# Sheet1.net
KiCad netlist of a schematic drawn in Altium Designer
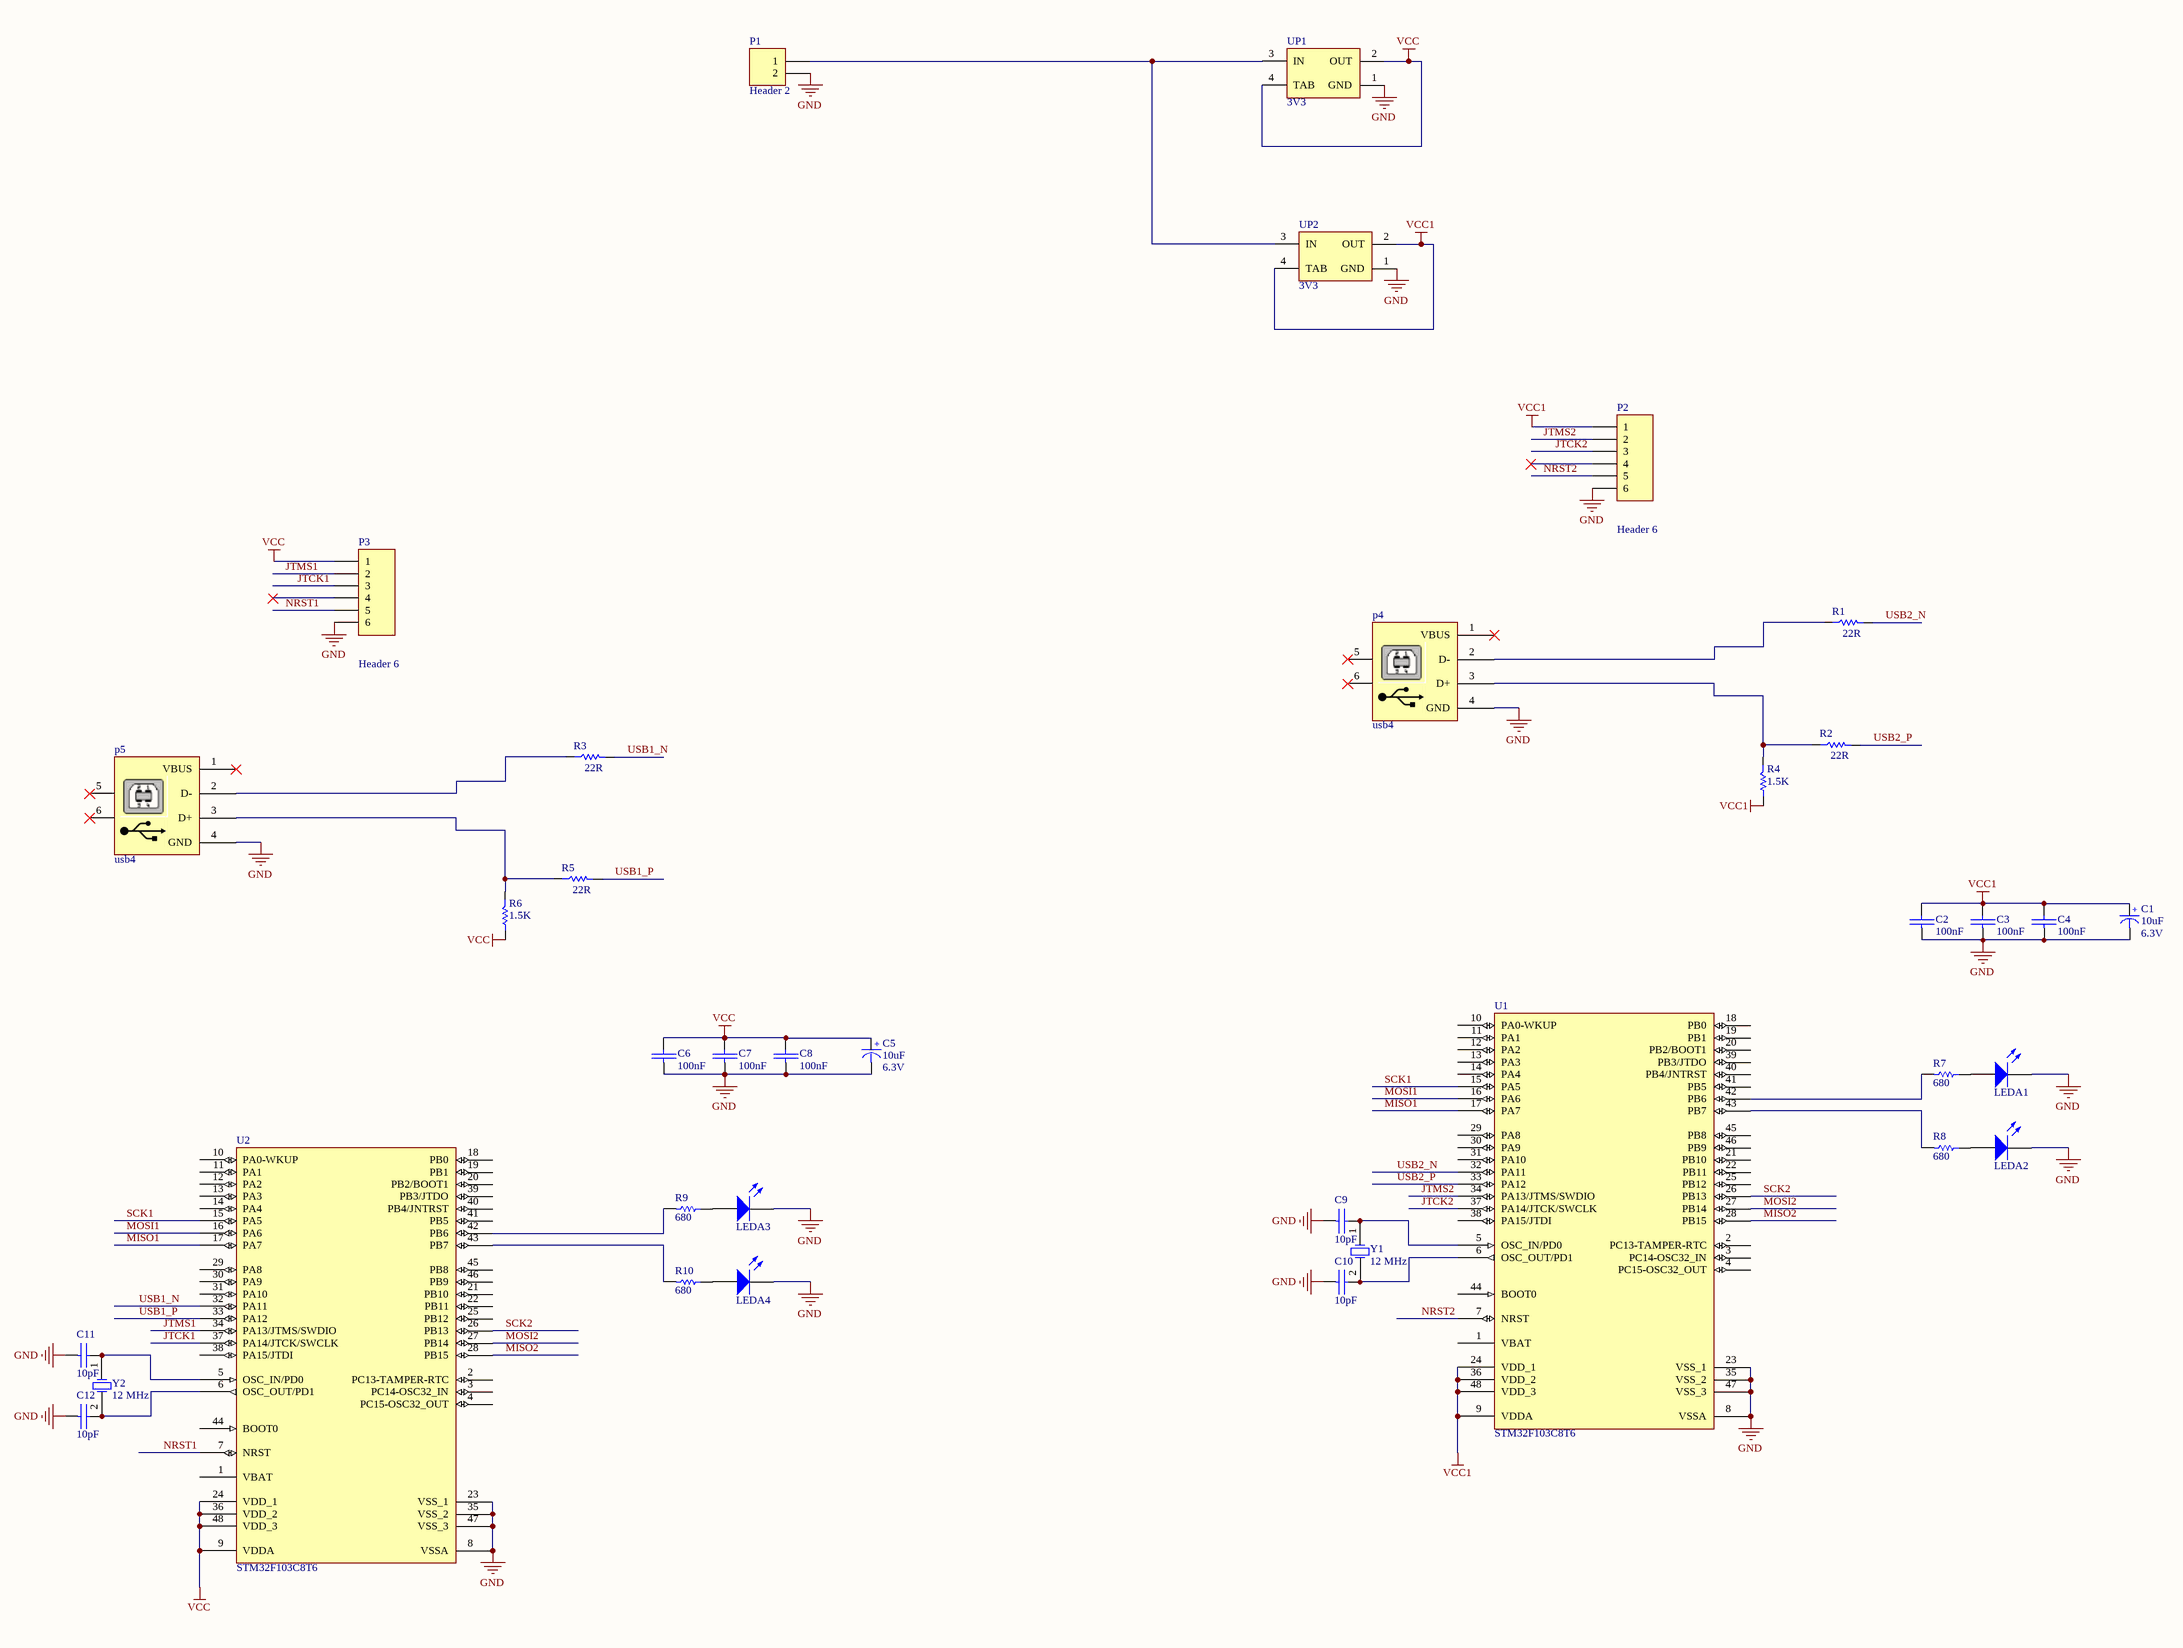
[diagram p0: Sheet1.SchDoc]

(export (version "E")
  (design (tool "Eeschema 10.0.6"))
  (components
    (comp (ref "C1")
      (value "10uF")
      (footprint "cap 01")
      (description "Polar Capacitor")
      (fields (field (name "VOLTAGE") "6.3V") (field (name "DESIGNER") "Saeid Jorablo"))
      (libsource (lib "My Library") (part "Cap-Polar"))
    )
    (comp (ref "C2")
      (value "100nF")
      (footprint "SMD_CAP_1206")
      (description "Bipolar Capacitor")
      (fields (field (name "VOLTAGE") "100V") (field (name "DESIGNER") "Saeid Jorablo"))
      (libsource (lib "My Library") (part "Cap-Bipolar"))
    )
    (comp (ref "C3")
      (value "100nF")
      (footprint "SMD_CAP_1206")
      (description "Bipolar Capacitor")
      (fields (field (name "VOLTAGE") "100V") (field (name "DESIGNER") "Saeid Jorablo"))
      (libsource (lib "My Library") (part "Cap-Bipolar"))
    )
    (comp (ref "C4")
      (value "100nF")
      (footprint "SMD_CAP_1206")
      (description "Bipolar Capacitor")
      (fields (field (name "VOLTAGE") "100V") (field (name "DESIGNER") "Saeid Jorablo"))
      (libsource (lib "My Library") (part "Cap-Bipolar"))
    )
    (comp (ref "C5")
      (value "10uF")
      (footprint "cap 01")
      (description "Polar Capacitor")
      (fields (field (name "VOLTAGE") "6.3V") (field (name "DESIGNER") "Saeid Jorablo"))
      (libsource (lib "My Library") (part "Cap-Polar"))
    )
    (comp (ref "C6")
      (value "100nF")
      (footprint "SMD_CAP_1206")
      (description "Bipolar Capacitor")
      (fields (field (name "VOLTAGE") "100V") (field (name "DESIGNER") "Saeid Jorablo"))
      (libsource (lib "My Library") (part "Cap-Bipolar"))
    )
    (comp (ref "C7")
      (value "100nF")
      (footprint "SMD_CAP_1206")
      (description "Bipolar Capacitor")
      (fields (field (name "VOLTAGE") "100V") (field (name "DESIGNER") "Saeid Jorablo"))
      (libsource (lib "My Library") (part "Cap-Bipolar"))
    )
    (comp (ref "C8")
      (value "100nF")
      (footprint "SMD_CAP_1206")
      (description "Bipolar Capacitor")
      (fields (field (name "VOLTAGE") "100V") (field (name "DESIGNER") "Saeid Jorablo"))
      (libsource (lib "My Library") (part "Cap-Bipolar"))
    )
    (comp (ref "C9")
      (value "10pF")
      (footprint "SMD_CAP_1206")
      (description "Bipolar Capacitor")
      (fields (field (name "VOLTAGE") "100V") (field (name "DESIGNER") "Saeid Jorablo"))
      (libsource (lib "My Library") (part "Cap-Bipolar"))
    )
    (comp (ref "C10")
      (value "10pF")
      (footprint "SMD_CAP_1206")
      (description "Bipolar Capacitor")
      (fields (field (name "VOLTAGE") "100V") (field (name "DESIGNER") "Saeid Jorablo"))
      (libsource (lib "My Library") (part "Cap-Bipolar"))
    )
    (comp (ref "C11")
      (value "10pF")
      (footprint "SMD_CAP_1206")
      (description "Bipolar Capacitor")
      (fields (field (name "VOLTAGE") "100V") (field (name "DESIGNER") "Saeid Jorablo"))
      (libsource (lib "My Library") (part "Cap-Bipolar"))
    )
    (comp (ref "C12")
      (value "10pF")
      (footprint "SMD_CAP_1206")
      (description "Bipolar Capacitor")
      (fields (field (name "VOLTAGE") "100V") (field (name "DESIGNER") "Saeid Jorablo"))
      (libsource (lib "My Library") (part "Cap-Bipolar"))
    )
    (comp (ref "LEDA1")
      (value "LED0")
      (footprint "SMD_08_05_LED")
      (description "Typical INFRARED GaAs LED")
      (fields (field (name "PUBLISHER") "Altium Limited"))
      (libsource (lib "*") (part "LED0"))
    )
    (comp (ref "LEDA2")
      (value "LED0")
      (footprint "SMD_08_05_LED")
      (description "Typical INFRARED GaAs LED")
      (fields (field (name "PUBLISHER") "Altium Limited"))
      (libsource (lib "*") (part "LED0"))
    )
    (comp (ref "LEDA3")
      (value "LED0")
      (footprint "SMD_08_05_LED")
      (description "Typical INFRARED GaAs LED")
      (fields (field (name "PUBLISHER") "Altium Limited"))
      (libsource (lib "*") (part "LED0"))
    )
    (comp (ref "LEDA4")
      (value "LED0")
      (footprint "SMD_08_05_LED")
      (description "Typical INFRARED GaAs LED")
      (fields (field (name "PUBLISHER") "Altium Limited"))
      (libsource (lib "*") (part "LED0"))
    )
    (comp (ref "P1")
      (value "Header 2")
      (footprint "TMS2-M/R")
      (description "Header, 2-Pin")
      (fields (field (name "PUBLISHER") "Altium Limited"))
      (libsource (lib "Miscellaneous Connectors") (part "Header 2"))
    )
    (comp (ref "P2")
      (value "Header 6")
      (footprint "HEADER 6X1")
      (description "Header, 6-Pin")
      (fields (field (name "PUBLISHER") "Altium Limited"))
      (libsource (lib "Miscellaneous Connectors") (part "Header 6"))
    )
    (comp (ref "P3")
      (value "Header 6")
      (footprint "HEADER 6X1")
      (description "Header, 6-Pin")
      (fields (field (name "PUBLISHER") "Altium Limited"))
      (libsource (lib "Miscellaneous Connectors") (part "Header 6"))
    )
    (comp (ref "p4")
      (value "usb4")
      (footprint "ConUSB_B_F")
      (description "USB Connector-B Type")
      (fields (field (name "DESIGNER") "Eng. Saeid Jorablo"))
      (libsource (lib "My Library") (part "USB"))
    )
    (comp (ref "p5")
      (value "usb4")
      (footprint "ConUSB_B_F")
      (description "USB Connector-B Type")
      (fields (field (name "DESIGNER") "Eng. Saeid Jorablo"))
      (libsource (lib "My Library") (part "USB"))
    )
    (comp (ref "R1")
      (value "22R")
      (footprint "SMD_RES_1206")
      (description "Resistor")
      (fields (field (name "TOLERANCE") "5%") (field (name "POWER") "1/8 W"))
      (libsource (lib "My Library") (part "Resistor"))
    )
    (comp (ref "R2")
      (value "22R")
      (footprint "SMD_RES_1206")
      (description "Resistor")
      (fields (field (name "TOLERANCE") "5%") (field (name "POWER") "1/8 W"))
      (libsource (lib "My Library") (part "Resistor"))
    )
    (comp (ref "R3")
      (value "22R")
      (footprint "SMD_RES_1206")
      (description "Resistor")
      (fields (field (name "TOLERANCE") "5%") (field (name "POWER") "1/8 W"))
      (libsource (lib "My Library") (part "Resistor"))
    )
    (comp (ref "R4")
      (value "1.5K")
      (footprint "SMD_RES_1206")
      (description "Resistor")
      (fields (field (name "TOLERANCE") "5%") (field (name "POWER") "1/8 W"))
      (libsource (lib "My Library") (part "Resistor"))
    )
    (comp (ref "R5")
      (value "22R")
      (footprint "SMD_RES_1206")
      (description "Resistor")
      (fields (field (name "TOLERANCE") "5%") (field (name "POWER") "1/8 W"))
      (libsource (lib "My Library") (part "Resistor"))
    )
    (comp (ref "R6")
      (value "1.5K")
      (footprint "SMD_RES_1206")
      (description "Resistor")
      (fields (field (name "TOLERANCE") "5%") (field (name "POWER") "1/8 W"))
      (libsource (lib "My Library") (part "Resistor"))
    )
    (comp (ref "R7")
      (value "680")
      (footprint "SMD_RES_1206")
      (description "Resistor")
      (fields (field (name "PUBLISHER") "Altium Limited"))
      (libsource (lib "Miscellaneous Devices") (part "Res1"))
    )
    (comp (ref "R8")
      (value "680")
      (footprint "SMD_RES_1206")
      (description "Resistor")
      (fields (field (name "PUBLISHER") "Altium Limited"))
      (libsource (lib "Miscellaneous Devices") (part "Res1"))
    )
    (comp (ref "R9")
      (value "680")
      (footprint "SMD_RES_1206")
      (description "Resistor")
      (fields (field (name "PUBLISHER") "Altium Limited"))
      (libsource (lib "Miscellaneous Devices") (part "Res1"))
    )
    (comp (ref "R10")
      (value "680")
      (footprint "SMD_RES_1206")
      (description "Resistor")
      (fields (field (name "PUBLISHER") "Altium Limited"))
      (libsource (lib "Miscellaneous Devices") (part "Res1"))
    )
    (comp (ref "U1")
      (value "STM32F103C8T6")
      (footprint "LQFP48_N")
      (description "STM32 ARM-based 32-bit MCU with 64 Kbytes Flash, 48-pin LQFP, Industrial Temperature")
      (fields (field (name "PUBLISHER") "Altium Limited"))
      (libsource (lib "ST Microcontroller 32-Bit STM32") (part "STM32F103C8T6"))
    )
    (comp (ref "U2")
      (value "STM32F103C8T6")
      (footprint "LQFP48_N")
      (description "STM32 ARM-based 32-bit MCU with 64 Kbytes Flash, 48-pin LQFP, Industrial Temperature")
      (fields (field (name "PUBLISHER") "Altium Limited"))
      (libsource (lib "ST Microcontroller 32-Bit STM32") (part "STM32F103C8T6"))
    )
    (comp (ref "UP1")
      (value "3V3")
      (footprint "SOT223")
      (description "x.x Volt, 800mA Low-Dropout Linear Regulator, 4-pin SOT-223")
      (fields (field (name "DESIGNER") "Ali Hafizi"))
      (libsource (lib "Altium") (part "AMS1117-x.x"))
    )
    (comp (ref "UP2")
      (value "3V3")
      (footprint "SOT223")
      (description "x.x Volt, 800mA Low-Dropout Linear Regulator, 4-pin SOT-223")
      (fields (field (name "DESIGNER") "Ali Hafizi"))
      (libsource (lib "Altium") (part "AMS1117-x.x"))
    )
    (comp (ref "Y1")
      (value "12 MHz")
      (footprint "XTAL")
      (description "XTAL Crystal")
      (libsource (lib "My Library") (part "XTAL"))
    )
    (comp (ref "Y2")
      (value "12 MHz")
      (footprint "XTAL")
      (description "XTAL Crystal")
      (libsource (lib "My Library") (part "XTAL"))
    )
  )
  (nets
    (net (code "1") (name "/JTCK1") (class "Default")
      (node (ref "P3") (pin "3") (pinfunction "3_3") (pintype "passive"))
      (node (ref "U2") (pin "37") (pinfunction "PA14/JTCK/SWCLK_37") (pintype "bidirectional"))
    )
    (net (code "2") (name "/JTCK2") (class "Default")
      (node (ref "P2") (pin "3") (pinfunction "3_3") (pintype "passive"))
      (node (ref "U1") (pin "37") (pinfunction "PA14/JTCK/SWCLK_37") (pintype "bidirectional"))
    )
    (net (code "3") (name "/JTMS1") (class "Default")
      (node (ref "P3") (pin "2") (pinfunction "2_2") (pintype "passive"))
      (node (ref "U2") (pin "34") (pinfunction "PA13/JTMS/SWDIO_34") (pintype "bidirectional"))
    )
    (net (code "4") (name "/JTMS2") (class "Default")
      (node (ref "P2") (pin "2") (pinfunction "2_2") (pintype "passive"))
      (node (ref "U1") (pin "34") (pinfunction "PA13/JTMS/SWDIO_34") (pintype "bidirectional"))
    )
    (net (code "5") (name "/MISO1") (class "Default")
      (node (ref "U1") (pin "17") (pinfunction "PA7_17") (pintype "bidirectional"))
      (node (ref "U2") (pin "17") (pinfunction "PA7_17") (pintype "bidirectional"))
    )
    (net (code "6") (name "/MISO2") (class "Default")
      (node (ref "U1") (pin "28") (pinfunction "PB15_28") (pintype "bidirectional"))
      (node (ref "U2") (pin "28") (pinfunction "PB15_28") (pintype "bidirectional"))
    )
    (net (code "7") (name "/MOSI1") (class "Default")
      (node (ref "U1") (pin "16") (pinfunction "PA6_16") (pintype "bidirectional"))
      (node (ref "U2") (pin "16") (pinfunction "PA6_16") (pintype "bidirectional"))
    )
    (net (code "8") (name "/MOSI2") (class "Default")
      (node (ref "U1") (pin "27") (pinfunction "PB14_27") (pintype "bidirectional"))
      (node (ref "U2") (pin "27") (pinfunction "PB14_27") (pintype "bidirectional"))
    )
    (net (code "9") (name "/NRST1") (class "Default")
      (node (ref "P3") (pin "5") (pinfunction "5_5") (pintype "passive"))
      (node (ref "U2") (pin "7") (pinfunction "NRST_7") (pintype "bidirectional"))
    )
    (net (code "10") (name "/NRST2") (class "Default")
      (node (ref "P2") (pin "5") (pinfunction "5_5") (pintype "passive"))
      (node (ref "U1") (pin "7") (pinfunction "NRST_7") (pintype "bidirectional"))
    )
    (net (code "11") (name "/SCK1") (class "Default")
      (node (ref "U1") (pin "15") (pinfunction "PA5_15") (pintype "bidirectional"))
      (node (ref "U2") (pin "15") (pinfunction "PA5_15") (pintype "bidirectional"))
    )
    (net (code "12") (name "/SCK2") (class "Default")
      (node (ref "U1") (pin "26") (pinfunction "PB13_26") (pintype "bidirectional"))
      (node (ref "U2") (pin "26") (pinfunction "PB13_26") (pintype "bidirectional"))
    )
    (net (code "13") (name "/USB1_N") (class "Default")
      (node (ref "R3") (pin "2") (pinfunction "2_2") (pintype "passive"))
      (node (ref "U2") (pin "32") (pinfunction "PA11_32") (pintype "bidirectional"))
    )
    (net (code "14") (name "/USB1_P") (class "Default")
      (node (ref "R5") (pin "2") (pinfunction "2_2") (pintype "passive"))
      (node (ref "U2") (pin "33") (pinfunction "PA12_33") (pintype "bidirectional"))
    )
    (net (code "15") (name "/USB2_N") (class "Default")
      (node (ref "R1") (pin "2") (pinfunction "2_2") (pintype "passive"))
      (node (ref "U1") (pin "32") (pinfunction "PA11_32") (pintype "bidirectional"))
    )
    (net (code "16") (name "/USB2_P") (class "Default")
      (node (ref "R2") (pin "2") (pinfunction "2_2") (pintype "passive"))
      (node (ref "U1") (pin "33") (pinfunction "PA12_33") (pintype "bidirectional"))
    )
    (net (code "17") (name "GND") (class "Default")
      (node (ref "C1") (pin "2") (pinfunction "-_2") (pintype "passive"))
      (node (ref "C10") (pin "2") (pinfunction "-_2") (pintype "passive"))
      (node (ref "C11") (pin "2") (pinfunction "-_2") (pintype "passive"))
      (node (ref "C12") (pin "2") (pinfunction "-_2") (pintype "passive"))
      (node (ref "C2") (pin "2") (pinfunction "-_2") (pintype "passive"))
      (node (ref "C3") (pin "2") (pinfunction "-_2") (pintype "passive"))
      (node (ref "C4") (pin "2") (pinfunction "-_2") (pintype "passive"))
      (node (ref "C5") (pin "2") (pinfunction "-_2") (pintype "passive"))
      (node (ref "C6") (pin "2") (pinfunction "-_2") (pintype "passive"))
      (node (ref "C7") (pin "2") (pinfunction "-_2") (pintype "passive"))
      (node (ref "C8") (pin "2") (pinfunction "-_2") (pintype "passive"))
      (node (ref "C9") (pin "2") (pinfunction "-_2") (pintype "passive"))
      (node (ref "LEDA1") (pin "2") (pinfunction "K_2") (pintype "passive"))
      (node (ref "LEDA2") (pin "2") (pinfunction "K_2") (pintype "passive"))
      (node (ref "LEDA3") (pin "2") (pinfunction "K_2") (pintype "passive"))
      (node (ref "LEDA4") (pin "2") (pinfunction "K_2") (pintype "passive"))
      (node (ref "P1") (pin "2") (pinfunction "2_2") (pintype "passive"))
      (node (ref "P2") (pin "6") (pinfunction "6_6") (pintype "passive"))
      (node (ref "P3") (pin "6") (pinfunction "6_6") (pintype "passive"))
      (node (ref "U1") (pin "23") (pinfunction "VSS_1_23") (pintype "power_in"))
      (node (ref "U1") (pin "35") (pinfunction "VSS_2_35") (pintype "power_in"))
      (node (ref "U1") (pin "47") (pinfunction "VSS_3_47") (pintype "power_in"))
      (node (ref "U1") (pin "8") (pinfunction "VSSA_8") (pintype "power_in"))
      (node (ref "U2") (pin "23") (pinfunction "VSS_1_23") (pintype "power_in"))
      (node (ref "U2") (pin "35") (pinfunction "VSS_2_35") (pintype "power_in"))
      (node (ref "U2") (pin "47") (pinfunction "VSS_3_47") (pintype "power_in"))
      (node (ref "U2") (pin "8") (pinfunction "VSSA_8") (pintype "power_in"))
      (node (ref "UP1") (pin "1") (pinfunction "GND_1") (pintype "power_in"))
      (node (ref "UP2") (pin "1") (pinfunction "GND_1") (pintype "power_in"))
      (node (ref "p4") (pin "4") (pinfunction "GND_4") (pintype "power_in"))
      (node (ref "p5") (pin "4") (pinfunction "GND_4") (pintype "power_in"))
    )
    (net (code "18") (name "Net-(C9-+)") (class "Default")
      (node (ref "C9") (pin "1") (pinfunction "+_1") (pintype "passive"))
      (node (ref "U1") (pin "5") (pinfunction "OSC_IN/PD0_5") (pintype "input"))
      (node (ref "Y1") (pin "1") (pinfunction "OSC1_1") (pintype "passive"))
    )
    (net (code "19") (name "Net-(C10-+)") (class "Default")
      (node (ref "C10") (pin "1") (pinfunction "+_1") (pintype "passive"))
      (node (ref "U1") (pin "6") (pinfunction "OSC_OUT/PD1_6") (pintype "output"))
      (node (ref "Y1") (pin "2") (pinfunction "OSC2_2") (pintype "passive"))
    )
    (net (code "20") (name "Net-(C11-+)") (class "Default")
      (node (ref "C11") (pin "1") (pinfunction "+_1") (pintype "passive"))
      (node (ref "U2") (pin "5") (pinfunction "OSC_IN/PD0_5") (pintype "input"))
      (node (ref "Y2") (pin "1") (pinfunction "OSC1_1") (pintype "passive"))
    )
    (net (code "21") (name "Net-(C12-+)") (class "Default")
      (node (ref "C12") (pin "1") (pinfunction "+_1") (pintype "passive"))
      (node (ref "U2") (pin "6") (pinfunction "OSC_OUT/PD1_6") (pintype "output"))
      (node (ref "Y2") (pin "2") (pinfunction "OSC2_2") (pintype "passive"))
    )
    (net (code "22") (name "Net-(LEDA1-A)") (class "Default")
      (node (ref "LEDA1") (pin "1") (pinfunction "A_1") (pintype "passive"))
      (node (ref "R7") (pin "1") (pinfunction "1_1") (pintype "passive"))
    )
    (net (code "23") (name "Net-(LEDA2-A)") (class "Default")
      (node (ref "LEDA2") (pin "1") (pinfunction "A_1") (pintype "passive"))
      (node (ref "R8") (pin "1") (pinfunction "1_1") (pintype "passive"))
    )
    (net (code "24") (name "Net-(LEDA3-A)") (class "Default")
      (node (ref "LEDA3") (pin "1") (pinfunction "A_1") (pintype "passive"))
      (node (ref "R9") (pin "1") (pinfunction "1_1") (pintype "passive"))
    )
    (net (code "25") (name "Net-(LEDA4-A)") (class "Default")
      (node (ref "LEDA4") (pin "1") (pinfunction "A_1") (pintype "passive"))
      (node (ref "R10") (pin "1") (pinfunction "1_1") (pintype "passive"))
    )
    (net (code "26") (name "Net-(U1-PB6)") (class "Default")
      (node (ref "R7") (pin "2") (pinfunction "2_2") (pintype "passive"))
      (node (ref "U1") (pin "42") (pinfunction "PB6_42") (pintype "bidirectional"))
    )
    (net (code "27") (name "Net-(U1-PB7)") (class "Default")
      (node (ref "R8") (pin "2") (pinfunction "2_2") (pintype "passive"))
      (node (ref "U1") (pin "43") (pinfunction "PB7_43") (pintype "bidirectional"))
    )
    (net (code "28") (name "Net-(U2-PB6)") (class "Default")
      (node (ref "R9") (pin "2") (pinfunction "2_2") (pintype "passive"))
      (node (ref "U2") (pin "42") (pinfunction "PB6_42") (pintype "bidirectional"))
    )
    (net (code "29") (name "Net-(U2-PB7)") (class "Default")
      (node (ref "R10") (pin "2") (pinfunction "2_2") (pintype "passive"))
      (node (ref "U2") (pin "43") (pinfunction "PB7_43") (pintype "bidirectional"))
    )
    (net (code "30") (name "Net-(UP1-IN)") (class "Default")
      (node (ref "P1") (pin "1") (pinfunction "1_1") (pintype "passive"))
      (node (ref "UP1") (pin "3") (pinfunction "IN_3") (pintype "power_in"))
      (node (ref "UP2") (pin "3") (pinfunction "IN_3") (pintype "power_in"))
    )
    (net (code "31") (name "Net-(p4-D+)") (class "Default")
      (node (ref "R2") (pin "1") (pinfunction "1_1") (pintype "passive"))
      (node (ref "R4") (pin "1") (pinfunction "1_1") (pintype "passive"))
      (node (ref "p4") (pin "3") (pinfunction "D+_3") (pintype "passive"))
    )
    (net (code "32") (name "Net-(p4-D-)") (class "Default")
      (node (ref "R1") (pin "1") (pinfunction "1_1") (pintype "passive"))
      (node (ref "p4") (pin "2") (pinfunction "D-_2") (pintype "passive"))
    )
    (net (code "33") (name "Net-(p5-D+)") (class "Default")
      (node (ref "R5") (pin "1") (pinfunction "1_1") (pintype "passive"))
      (node (ref "R6") (pin "1") (pinfunction "1_1") (pintype "passive"))
      (node (ref "p5") (pin "3") (pinfunction "D+_3") (pintype "passive"))
    )
    (net (code "34") (name "Net-(p5-D-)") (class "Default")
      (node (ref "R3") (pin "1") (pinfunction "1_1") (pintype "passive"))
      (node (ref "p5") (pin "2") (pinfunction "D-_2") (pintype "passive"))
    )
    (net (code "35") (name "VCC") (class "Default")
      (node (ref "C5") (pin "1") (pinfunction "+_1") (pintype "passive"))
      (node (ref "C6") (pin "1") (pinfunction "+_1") (pintype "passive"))
      (node (ref "C7") (pin "1") (pinfunction "+_1") (pintype "passive"))
      (node (ref "C8") (pin "1") (pinfunction "+_1") (pintype "passive"))
      (node (ref "P3") (pin "1") (pinfunction "1_1") (pintype "passive"))
      (node (ref "R6") (pin "2") (pinfunction "2_2") (pintype "passive"))
      (node (ref "U2") (pin "24") (pinfunction "VDD_1_24") (pintype "power_in"))
      (node (ref "U2") (pin "36") (pinfunction "VDD_2_36") (pintype "power_in"))
      (node (ref "U2") (pin "48") (pinfunction "VDD_3_48") (pintype "power_in"))
      (node (ref "U2") (pin "9") (pinfunction "VDDA_9") (pintype "power_in"))
      (node (ref "UP1") (pin "2") (pinfunction "OUT_2") (pintype "power_in"))
      (node (ref "UP1") (pin "4") (pinfunction "TAB_4") (pintype "power_in"))
    )
    (net (code "36") (name "VCC1") (class "Default")
      (node (ref "C1") (pin "1") (pinfunction "+_1") (pintype "passive"))
      (node (ref "C2") (pin "1") (pinfunction "+_1") (pintype "passive"))
      (node (ref "C3") (pin "1") (pinfunction "+_1") (pintype "passive"))
      (node (ref "C4") (pin "1") (pinfunction "+_1") (pintype "passive"))
      (node (ref "P2") (pin "1") (pinfunction "1_1") (pintype "passive"))
      (node (ref "R4") (pin "2") (pinfunction "2_2") (pintype "passive"))
      (node (ref "U1") (pin "24") (pinfunction "VDD_1_24") (pintype "power_in"))
      (node (ref "U1") (pin "36") (pinfunction "VDD_2_36") (pintype "power_in"))
      (node (ref "U1") (pin "48") (pinfunction "VDD_3_48") (pintype "power_in"))
      (node (ref "U1") (pin "9") (pinfunction "VDDA_9") (pintype "power_in"))
      (node (ref "UP2") (pin "2") (pinfunction "OUT_2") (pintype "power_in"))
      (node (ref "UP2") (pin "4") (pinfunction "TAB_4") (pintype "power_in"))
    )
    (net (code "37") (name "unconnected-(P2-Pad4)") (class "Default")
      (node (ref "P2") (pin "4") (pinfunction "4_4") (pintype "passive+no_connect"))
    )
    (net (code "38") (name "unconnected-(P3-Pad4)") (class "Default")
      (node (ref "P3") (pin "4") (pinfunction "4_4") (pintype "passive+no_connect"))
    )
    (net (code "39") (name "unconnected-(U1-BOOT0-Pad44)") (class "Default")
      (node (ref "U1") (pin "44") (pinfunction "BOOT0_44") (pintype "input"))
    )
    (net (code "40") (name "unconnected-(U1-PA0-WKUP-Pad10)") (class "Default")
      (node (ref "U1") (pin "10") (pinfunction "PA0-WKUP_10") (pintype "bidirectional"))
    )
    (net (code "41") (name "unconnected-(U1-PA1-Pad11)") (class "Default")
      (node (ref "U1") (pin "11") (pinfunction "PA1_11") (pintype "bidirectional"))
    )
    (net (code "42") (name "unconnected-(U1-PA2-Pad12)") (class "Default")
      (node (ref "U1") (pin "12") (pinfunction "PA2_12") (pintype "bidirectional"))
    )
    (net (code "43") (name "unconnected-(U1-PA3-Pad13)") (class "Default")
      (node (ref "U1") (pin "13") (pinfunction "PA3_13") (pintype "bidirectional"))
    )
    (net (code "44") (name "unconnected-(U1-PA4-Pad14)") (class "Default")
      (node (ref "U1") (pin "14") (pinfunction "PA4_14") (pintype "bidirectional"))
    )
    (net (code "45") (name "unconnected-(U1-PA8-Pad29)") (class "Default")
      (node (ref "U1") (pin "29") (pinfunction "PA8_29") (pintype "bidirectional"))
    )
    (net (code "46") (name "unconnected-(U1-PA9-Pad30)") (class "Default")
      (node (ref "U1") (pin "30") (pinfunction "PA9_30") (pintype "bidirectional"))
    )
    (net (code "47") (name "unconnected-(U1-PA10-Pad31)") (class "Default")
      (node (ref "U1") (pin "31") (pinfunction "PA10_31") (pintype "bidirectional"))
    )
    (net (code "48") (name "unconnected-(U1-PA15{slash}JTDI-Pad38)") (class "Default")
      (node (ref "U1") (pin "38") (pinfunction "PA15/JTDI_38") (pintype "bidirectional"))
    )
    (net (code "49") (name "unconnected-(U1-PB0-Pad18)") (class "Default")
      (node (ref "U1") (pin "18") (pinfunction "PB0_18") (pintype "bidirectional"))
    )
    (net (code "50") (name "unconnected-(U1-PB1-Pad19)") (class "Default")
      (node (ref "U1") (pin "19") (pinfunction "PB1_19") (pintype "bidirectional"))
    )
    (net (code "51") (name "unconnected-(U1-PB2{slash}BOOT1-Pad20)") (class "Default")
      (node (ref "U1") (pin "20") (pinfunction "PB2/BOOT1_20") (pintype "bidirectional"))
    )
    (net (code "52") (name "unconnected-(U1-PB3{slash}JTDO-Pad39)") (class "Default")
      (node (ref "U1") (pin "39") (pinfunction "PB3/JTDO_39") (pintype "bidirectional"))
    )
    (net (code "53") (name "unconnected-(U1-PB4{slash}JNTRST-Pad40)") (class "Default")
      (node (ref "U1") (pin "40") (pinfunction "PB4/JNTRST_40") (pintype "bidirectional"))
    )
    (net (code "54") (name "unconnected-(U1-PB5-Pad41)") (class "Default")
      (node (ref "U1") (pin "41") (pinfunction "PB5_41") (pintype "bidirectional"))
    )
    (net (code "55") (name "unconnected-(U1-PB8-Pad45)") (class "Default")
      (node (ref "U1") (pin "45") (pinfunction "PB8_45") (pintype "bidirectional"))
    )
    (net (code "56") (name "unconnected-(U1-PB9-Pad46)") (class "Default")
      (node (ref "U1") (pin "46") (pinfunction "PB9_46") (pintype "bidirectional"))
    )
    (net (code "57") (name "unconnected-(U1-PB10-Pad21)") (class "Default")
      (node (ref "U1") (pin "21") (pinfunction "PB10_21") (pintype "bidirectional"))
    )
    (net (code "58") (name "unconnected-(U1-PB11-Pad22)") (class "Default")
      (node (ref "U1") (pin "22") (pinfunction "PB11_22") (pintype "bidirectional"))
    )
    (net (code "59") (name "unconnected-(U1-PB12-Pad25)") (class "Default")
      (node (ref "U1") (pin "25") (pinfunction "PB12_25") (pintype "bidirectional"))
    )
    (net (code "60") (name "unconnected-(U1-PC13-TAMPER-RTC-Pad2)") (class "Default")
      (node (ref "U1") (pin "2") (pinfunction "PC13-TAMPER-RTC_2") (pintype "bidirectional"))
    )
    (net (code "61") (name "unconnected-(U1-PC14-OSC32_IN-Pad3)") (class "Default")
      (node (ref "U1") (pin "3") (pinfunction "PC14-OSC32_IN_3") (pintype "bidirectional"))
    )
    (net (code "62") (name "unconnected-(U1-PC15-OSC32_OUT-Pad4)") (class "Default")
      (node (ref "U1") (pin "4") (pinfunction "PC15-OSC32_OUT_4") (pintype "bidirectional"))
    )
    (net (code "63") (name "unconnected-(U1-VBAT-Pad1)") (class "Default")
      (node (ref "U1") (pin "1") (pinfunction "VBAT_1") (pintype "power_in"))
    )
    (net (code "64") (name "unconnected-(U2-BOOT0-Pad44)") (class "Default")
      (node (ref "U2") (pin "44") (pinfunction "BOOT0_44") (pintype "input"))
    )
    (net (code "65") (name "unconnected-(U2-PA0-WKUP-Pad10)") (class "Default")
      (node (ref "U2") (pin "10") (pinfunction "PA0-WKUP_10") (pintype "bidirectional"))
    )
    (net (code "66") (name "unconnected-(U2-PA1-Pad11)") (class "Default")
      (node (ref "U2") (pin "11") (pinfunction "PA1_11") (pintype "bidirectional"))
    )
    (net (code "67") (name "unconnected-(U2-PA2-Pad12)") (class "Default")
      (node (ref "U2") (pin "12") (pinfunction "PA2_12") (pintype "bidirectional"))
    )
    (net (code "68") (name "unconnected-(U2-PA3-Pad13)") (class "Default")
      (node (ref "U2") (pin "13") (pinfunction "PA3_13") (pintype "bidirectional"))
    )
    (net (code "69") (name "unconnected-(U2-PA4-Pad14)") (class "Default")
      (node (ref "U2") (pin "14") (pinfunction "PA4_14") (pintype "bidirectional"))
    )
    (net (code "70") (name "unconnected-(U2-PA8-Pad29)") (class "Default")
      (node (ref "U2") (pin "29") (pinfunction "PA8_29") (pintype "bidirectional"))
    )
    (net (code "71") (name "unconnected-(U2-PA9-Pad30)") (class "Default")
      (node (ref "U2") (pin "30") (pinfunction "PA9_30") (pintype "bidirectional"))
    )
    (net (code "72") (name "unconnected-(U2-PA10-Pad31)") (class "Default")
      (node (ref "U2") (pin "31") (pinfunction "PA10_31") (pintype "bidirectional"))
    )
    (net (code "73") (name "unconnected-(U2-PA15{slash}JTDI-Pad38)") (class "Default")
      (node (ref "U2") (pin "38") (pinfunction "PA15/JTDI_38") (pintype "bidirectional"))
    )
    (net (code "74") (name "unconnected-(U2-PB0-Pad18)") (class "Default")
      (node (ref "U2") (pin "18") (pinfunction "PB0_18") (pintype "bidirectional"))
    )
    (net (code "75") (name "unconnected-(U2-PB1-Pad19)") (class "Default")
      (node (ref "U2") (pin "19") (pinfunction "PB1_19") (pintype "bidirectional"))
    )
    (net (code "76") (name "unconnected-(U2-PB2{slash}BOOT1-Pad20)") (class "Default")
      (node (ref "U2") (pin "20") (pinfunction "PB2/BOOT1_20") (pintype "bidirectional"))
    )
    (net (code "77") (name "unconnected-(U2-PB3{slash}JTDO-Pad39)") (class "Default")
      (node (ref "U2") (pin "39") (pinfunction "PB3/JTDO_39") (pintype "bidirectional"))
    )
    (net (code "78") (name "unconnected-(U2-PB4{slash}JNTRST-Pad40)") (class "Default")
      (node (ref "U2") (pin "40") (pinfunction "PB4/JNTRST_40") (pintype "bidirectional"))
    )
    (net (code "79") (name "unconnected-(U2-PB5-Pad41)") (class "Default")
      (node (ref "U2") (pin "41") (pinfunction "PB5_41") (pintype "bidirectional"))
    )
    (net (code "80") (name "unconnected-(U2-PB8-Pad45)") (class "Default")
      (node (ref "U2") (pin "45") (pinfunction "PB8_45") (pintype "bidirectional"))
    )
    (net (code "81") (name "unconnected-(U2-PB9-Pad46)") (class "Default")
      (node (ref "U2") (pin "46") (pinfunction "PB9_46") (pintype "bidirectional"))
    )
    (net (code "82") (name "unconnected-(U2-PB10-Pad21)") (class "Default")
      (node (ref "U2") (pin "21") (pinfunction "PB10_21") (pintype "bidirectional"))
    )
    (net (code "83") (name "unconnected-(U2-PB11-Pad22)") (class "Default")
      (node (ref "U2") (pin "22") (pinfunction "PB11_22") (pintype "bidirectional"))
    )
    (net (code "84") (name "unconnected-(U2-PB12-Pad25)") (class "Default")
      (node (ref "U2") (pin "25") (pinfunction "PB12_25") (pintype "bidirectional"))
    )
    (net (code "85") (name "unconnected-(U2-PC13-TAMPER-RTC-Pad2)") (class "Default")
      (node (ref "U2") (pin "2") (pinfunction "PC13-TAMPER-RTC_2") (pintype "bidirectional"))
    )
    (net (code "86") (name "unconnected-(U2-PC14-OSC32_IN-Pad3)") (class "Default")
      (node (ref "U2") (pin "3") (pinfunction "PC14-OSC32_IN_3") (pintype "bidirectional"))
    )
    (net (code "87") (name "unconnected-(U2-PC15-OSC32_OUT-Pad4)") (class "Default")
      (node (ref "U2") (pin "4") (pinfunction "PC15-OSC32_OUT_4") (pintype "bidirectional"))
    )
    (net (code "88") (name "unconnected-(U2-VBAT-Pad1)") (class "Default")
      (node (ref "U2") (pin "1") (pinfunction "VBAT_1") (pintype "power_in"))
    )
    (net (code "89") (name "unconnected-(p4-Pad5)") (class "Default")
      (node (ref "p4") (pin "5") (pinfunction "5_5") (pintype "passive+no_connect"))
    )
    (net (code "90") (name "unconnected-(p4-Pad6)") (class "Default")
      (node (ref "p4") (pin "6") (pinfunction "6_6") (pintype "passive+no_connect"))
    )
    (net (code "91") (name "unconnected-(p4-VBUS-Pad1)") (class "Default")
      (node (ref "p4") (pin "1") (pinfunction "VBUS_1") (pintype "power_in+no_connect"))
    )
    (net (code "92") (name "unconnected-(p5-Pad5)") (class "Default")
      (node (ref "p5") (pin "5") (pinfunction "5_5") (pintype "passive+no_connect"))
    )
    (net (code "93") (name "unconnected-(p5-Pad6)") (class "Default")
      (node (ref "p5") (pin "6") (pinfunction "6_6") (pintype "passive+no_connect"))
    )
    (net (code "94") (name "unconnected-(p5-VBUS-Pad1)") (class "Default")
      (node (ref "p5") (pin "1") (pinfunction "VBUS_1") (pintype "power_in+no_connect"))
    )
  )
)
